# PWU_soldeerbout.net
KiCad netlist of a schematic drawn in Altium Designer
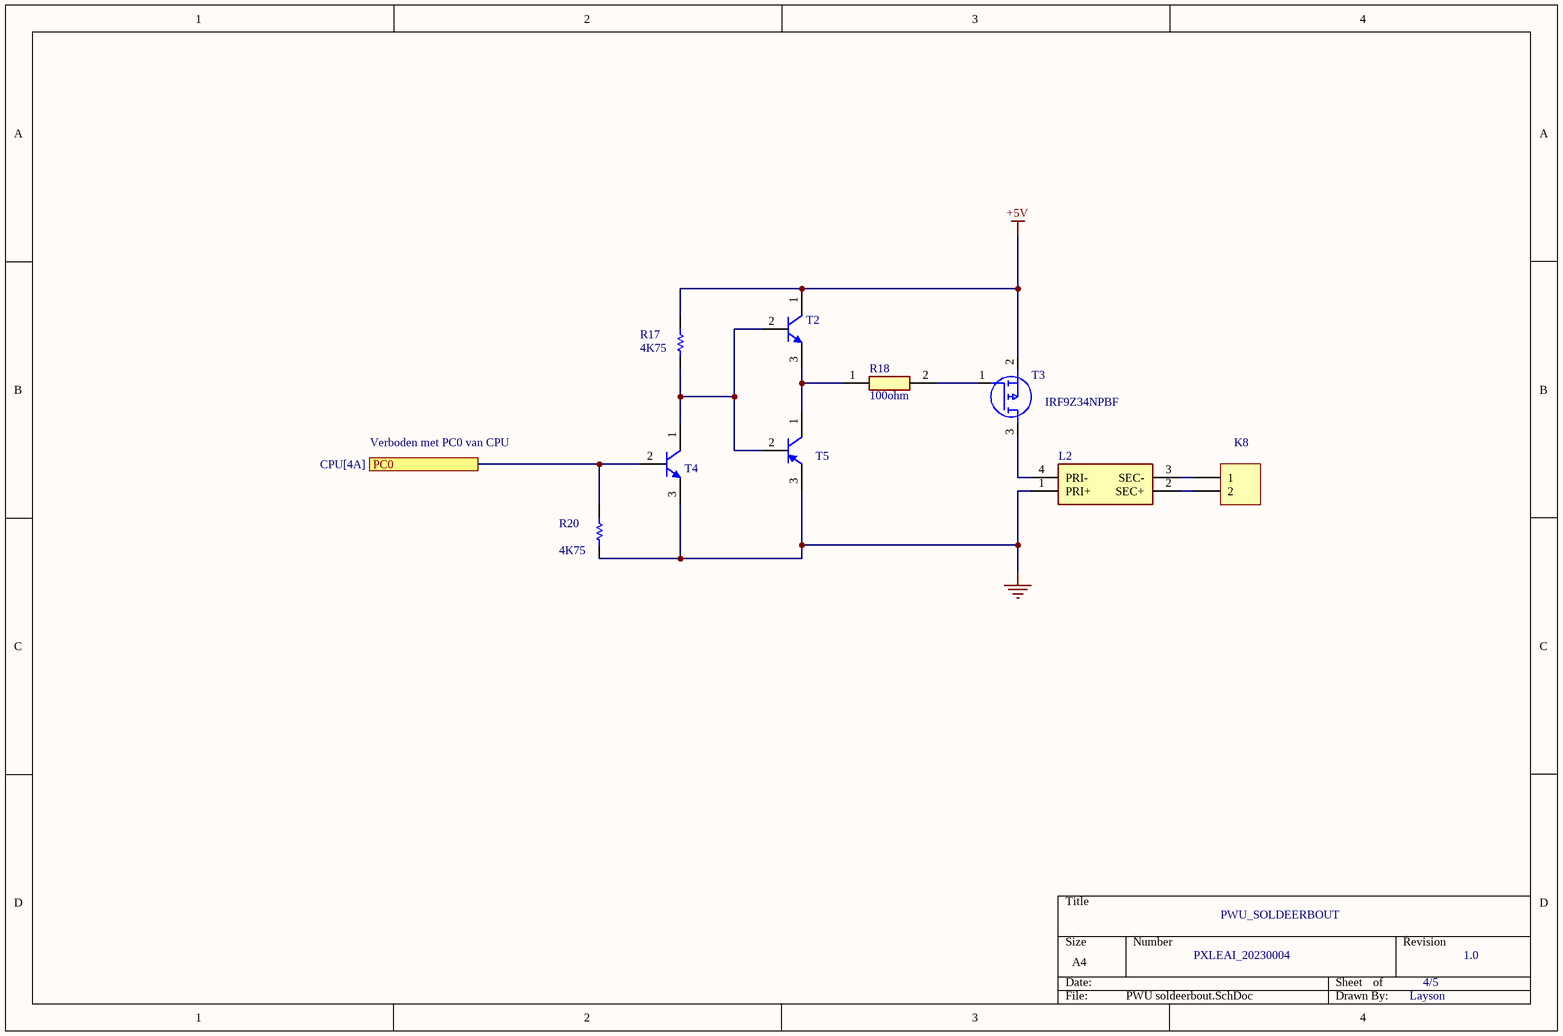
[diagram p0: PWU soldeerbout.SchDoc]

(export (version "E")
  (design (tool "Eeschema 10.0.6"))
  (components
    (comp (ref "K8")
      (value "Header 2")
      (footprint "HDR1X2")
      (description "Header, 2-Pin")
      (fields (field (name "PUBLISHER") "Altium Limited"))
      (libsource (lib "Miscellaneous Connectors") (part "Header 2"))
    )
    (comp (ref "L2")
      (value "CM2545X171B-10")
      (footprint "SamacSys:CM2545X171B10")
      (description "Transformer")
      (libsource (lib "*") (part "CM2545X171B-10"))
    )
    (comp (ref "R17")
      (value "4K75")
      (footprint "RESA60-630X240")
      (description "Axial Resistor, 4.75 KOhm, +/- 1%, 0.25 W, -55 to 155 degC, 2-Pin THD, RoHS, Bulk")
      (fields (field (name "TOLERANCE") "10%"))
      (libsource (lib "Altium Content Vault") (part "RES-2"))
    )
    (comp (ref "R18")
      (value "100ohm")
      (footprint "SamacSys:RESC2012X60N")
      (description "Resistor\r\nCR0805-JW-101ELF")
      (fields
        (field (name "MANUFACTURER_PART_NUMBER") "CR0805-JW-101ELF")
        (field (name "MOUSER PART NUMBER") "652-CR0805JW-101ELF")
      )
      (libsource (lib "*") (part "CR0805-JW-101ELF"))
    )
    (comp (ref "R20")
      (value "4K75")
      (footprint "RESA60-630X240")
      (description "Axial Resistor, 4.75 KOhm, +/- 1%, 0.25 W, -55 to 155 degC, 2-Pin THD, RoHS, Bulk")
      (fields (field (name "TOLERANCE") "10%"))
      (libsource (lib "Altium Content Vault") (part "RES-2"))
    )
    (comp (ref "T2")
      (value "BC547B")
      (footprint "ONSC-TO-92-3-29-11")
      (description "Amplifier Transistor, NPN Silicon, 3-Pin TO-92, Bulk Box")
      (fields (field (name "MANUFACTURER") "On Semiconductor"))
      (libsource (lib "Altium Content Vault") (part "ONSC-NPN-C1B2E3-3"))
    )
    (comp (ref "T3")
      (value "IRF9Z34NPBF")
      (footprint "TO254P469X1042X1967-3P")
      (description "MOSFET MOSFT PCh -55V -17A 100mOhm 23.3nC")
      (fields (field (name "MOUSER PART NUMBER") "942-IRF9Z34NPBF"))
      (libsource (lib "Soldeerstation") (part "IRF9Z34NPBF"))
    )
    (comp (ref "T4")
      (value "T4")
      (footprint "ONSC-TO-92-3-29-11")
      (description "Amplifier Transistor, NPN Silicon, 3-Pin TO-92, Bulk Box")
      (fields (field (name "MANUFACTURER") "On Semiconductor") (field (name "PARTNUMBER") "BC547B"))
      (libsource (lib "Altium Content Vault") (part "ONSC-NPN-C1B2E3-3"))
    )
    (comp (ref "T5")
      (value "T5")
      (footprint "ONSC-TO-92-3-29-11_AM_BL")
      (description "Amplifier Transistor, PNP Silicon, 3-Pin TO-92, Pb-Free, Ammo Box")
      (fields (field (name "PARTNUMBER") "BC557AZL1G") (field (name "MANUFACTURER") "On Semiconductor"))
      (libsource (lib "Altium Content Vault") (part "ONSC-PNP-C1B2E3-3"))
    )
  )
  (nets
    (net (code "1") (name "+5V") (class "Default")
      (node (ref "R17") (pin "1") (pinfunction "1_1") (pintype "passive"))
      (node (ref "T2") (pin "1") (pinfunction "C_1") (pintype "passive"))
      (node (ref "T3") (pin "2") (pinfunction "S_2") (pintype "passive"))
    )
    (net (code "2") (name "/PC0") (class "Default")
      (node (ref "R20") (pin "2") (pinfunction "2_2") (pintype "passive"))
      (node (ref "T4") (pin "2") (pinfunction "B_2") (pintype "passive"))
    )
    (net (code "3") (name "GND") (class "Default")
      (node (ref "L2") (pin "1") (pinfunction "PRI+_1") (pintype "passive"))
      (node (ref "R20") (pin "1") (pinfunction "1_1") (pintype "passive"))
      (node (ref "T4") (pin "3") (pinfunction "E_3") (pintype "passive"))
      (node (ref "T5") (pin "3") (pinfunction "E_3") (pintype "passive"))
    )
    (net (code "4") (name "Net-(L2-PRI-)") (class "Default")
      (node (ref "L2") (pin "4") (pinfunction "PRI-_4") (pintype "passive"))
      (node (ref "T3") (pin "3") (pinfunction "D_3") (pintype "passive"))
    )
    (net (code "5") (name "Net-(L2-SEC+)") (class "Default")
      (node (ref "K8") (pin "2") (pinfunction "2_2") (pintype "passive"))
      (node (ref "L2") (pin "2") (pinfunction "SEC+_2") (pintype "passive"))
    )
    (net (code "6") (name "Net-(L2-SEC-)") (class "Default")
      (node (ref "K8") (pin "1") (pinfunction "1_1") (pintype "passive"))
      (node (ref "L2") (pin "3") (pinfunction "SEC-_3") (pintype "passive"))
    )
    (net (code "7") (name "Net-(T2-B)") (class "Default")
      (node (ref "R17") (pin "2") (pinfunction "2_2") (pintype "passive"))
      (node (ref "T2") (pin "2") (pinfunction "B_2") (pintype "passive"))
      (node (ref "T4") (pin "1") (pinfunction "C_1") (pintype "passive"))
      (node (ref "T5") (pin "2") (pinfunction "B_2") (pintype "passive"))
    )
    (net (code "8") (name "Net-(T2-E)") (class "Default")
      (node (ref "R18") (pin "1") (pinfunction "1_1") (pintype "passive"))
      (node (ref "T2") (pin "3") (pinfunction "E_3") (pintype "passive"))
      (node (ref "T5") (pin "1") (pinfunction "C_1") (pintype "passive"))
    )
    (net (code "9") (name "Net-(T3-G)") (class "Default")
      (node (ref "R18") (pin "2") (pinfunction "2_2") (pintype "passive"))
      (node (ref "T3") (pin "1") (pinfunction "G_1") (pintype "passive"))
    )
  )
)
